# 4_RK3399_EMMC_ADC_PCIE.net
KiCad netlist of a schematic drawn in Altium Designer
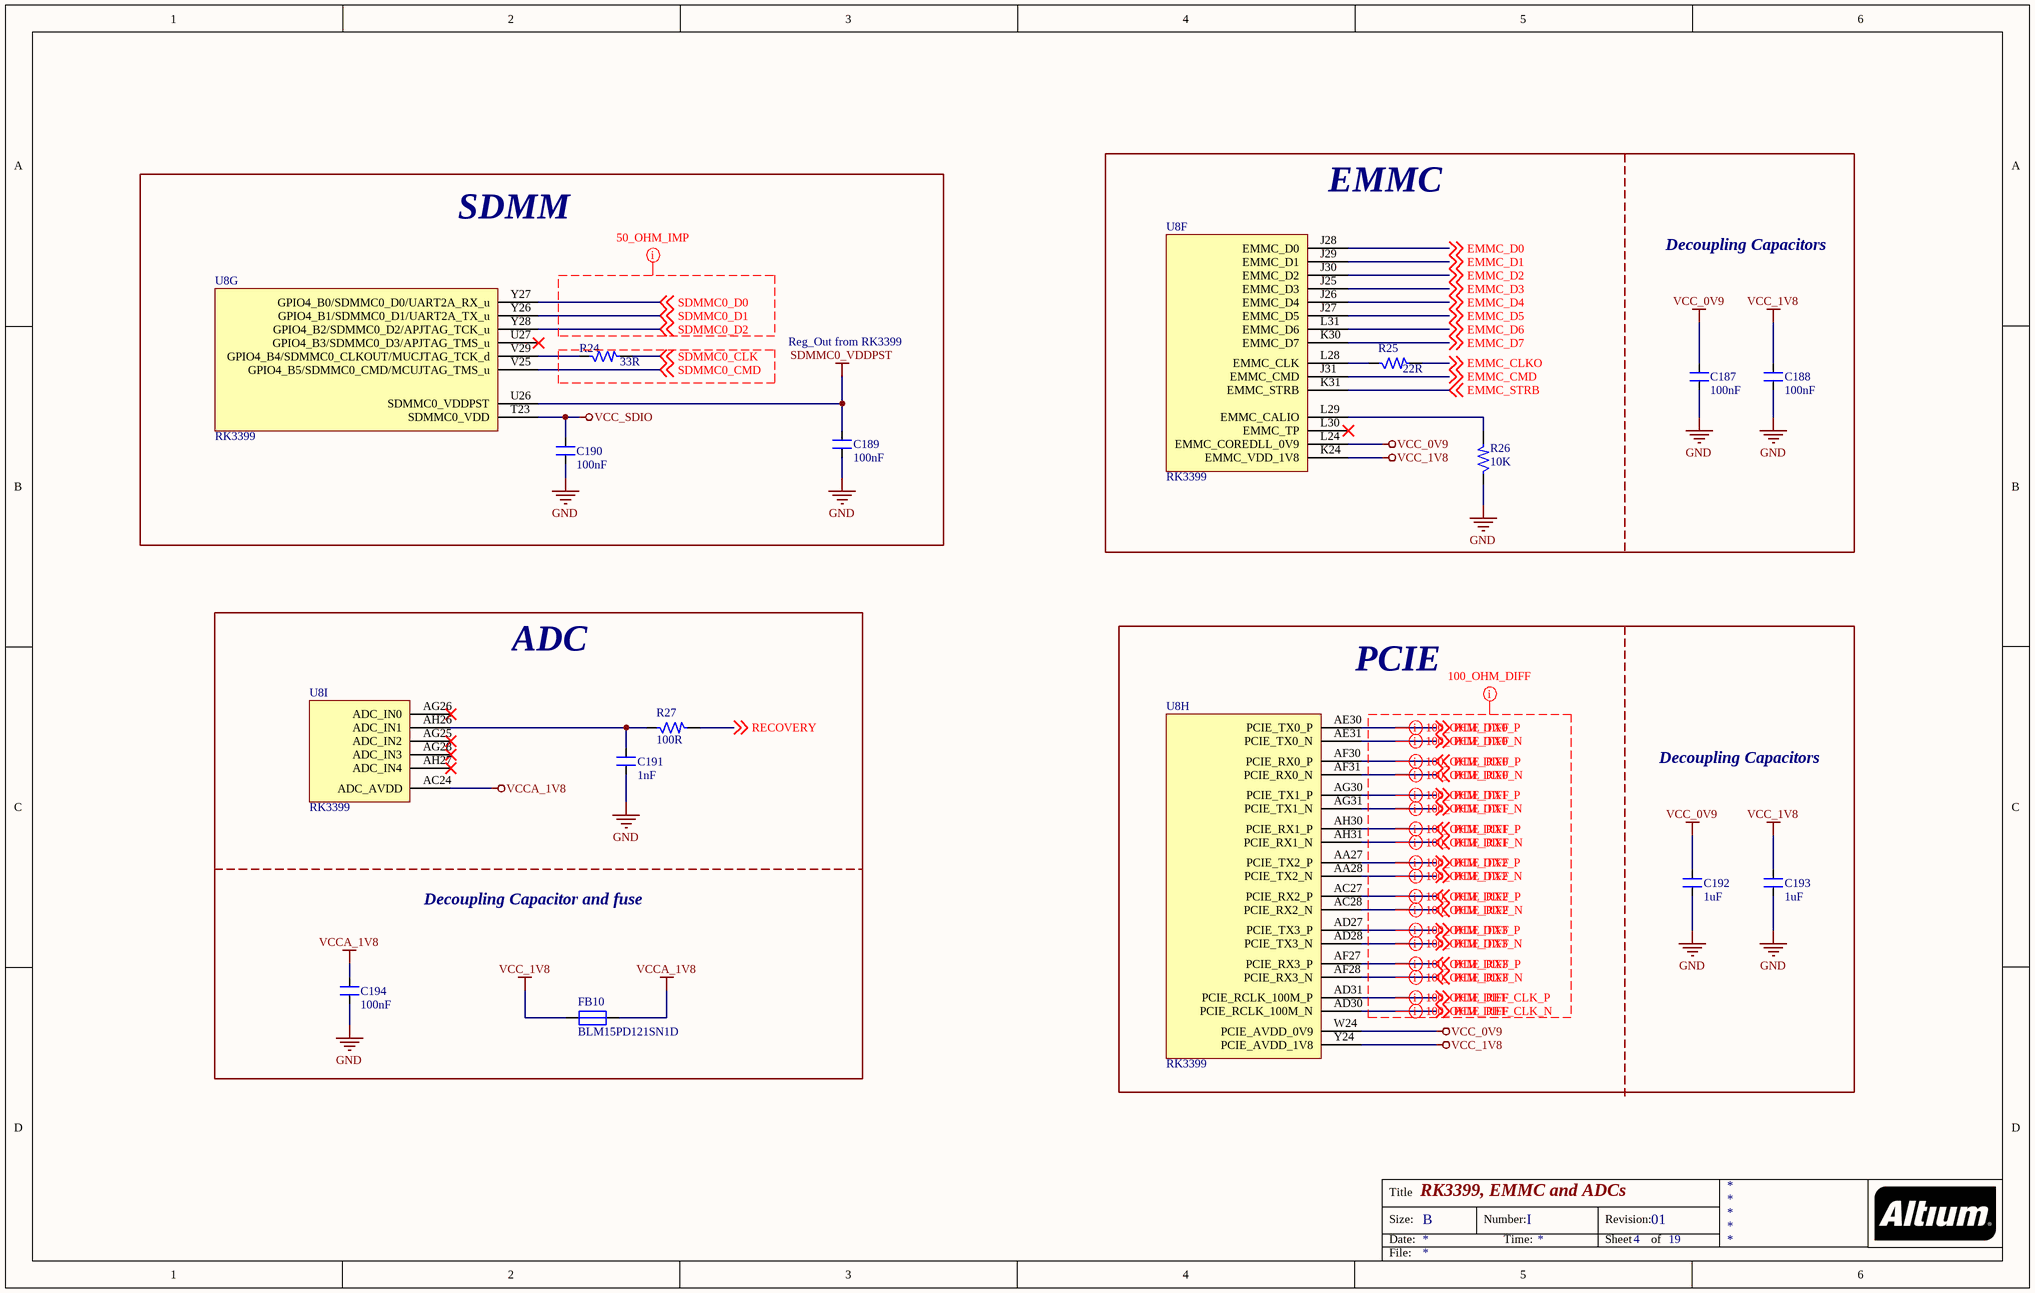
[diagram p0: [4] RK3399_EMMC_ADC_PCIE.SchDoc]

(export (version "E")
  (design (tool "Eeschema 10.0.6"))
  (components
    (comp (ref "C187")
      (value "100nF")
      (footprint "CAP_0201")
      (description "0.1µF ±10% 25V Ceramic Capacitor X5R 0201 (0603 Metric)")
      (fields
        (field (name "MANUFACTURER") "TDK Corporation")
        (field (name "MANUFACTURER PART NUMBER") "C0603X5R1E104K030BB")
      )
      (libsource (lib "EsteemPCB_SOM_Course_intlib") (part "CAP_100nF-25V-10%-0201"))
    )
    (comp (ref "C188")
      (value "100nF")
      (footprint "CAP_0201")
      (description "0.1µF ±10% 25V Ceramic Capacitor X5R 0201 (0603 Metric)")
      (fields
        (field (name "MANUFACTURER") "TDK Corporation")
        (field (name "MANUFACTURER PART NUMBER") "C0603X5R1E104K030BB")
      )
      (libsource (lib "EsteemPCB_SOM_Course_intlib") (part "CAP_100nF-25V-10%-0201"))
    )
    (comp (ref "C189")
      (value "100nF")
      (footprint "CAP_0201")
      (description "0.1µF ±10% 25V Ceramic Capacitor X5R 0201 (0603 Metric)")
      (fields
        (field (name "MANUFACTURER") "TDK Corporation")
        (field (name "MANUFACTURER PART NUMBER") "C0603X5R1E104K030BB")
      )
      (libsource (lib "EsteemPCB_SOM_Course_intlib") (part "CAP_100nF-25V-10%-0201"))
    )
    (comp (ref "C190")
      (value "100nF")
      (footprint "CAP_0201")
      (description "0.1µF ±10% 25V Ceramic Capacitor X5R 0201 (0603 Metric)")
      (fields
        (field (name "MANUFACTURER") "TDK Corporation")
        (field (name "MANUFACTURER PART NUMBER") "C0603X5R1E104K030BB")
      )
      (libsource (lib "EsteemPCB_SOM_Course_intlib") (part "CAP_100nF-25V-10%-0201"))
    )
    (comp (ref "C191")
      (value "1nF")
      (footprint "CAP_0201")
      (description "1000pF ±10% 16V Ceramic Capacitor X7R 0201 (0603 Metric)")
      (fields
        (field (name "MANUFACTURER") "Murata Electronics")
        (field (name "MANUFACTURER PART NUMBER") "GRM033R71C102KA01D")
      )
      (libsource (lib "EsteemPCB_SOM_Course_intlib") (part "CAP_1nF-16V-10%-0201"))
    )
    (comp (ref "C192")
      (value "1uF")
      (footprint "CAP_0201")
      (description "1µF ±20% 16V Ceramic Capacitor X5R 0201 (0603 Metric)")
      (fields
        (field (name "MANUFACTURER") "Samsung Electro-Mechanics")
        (field (name "MANUFACTURER PART NUMBER") "CL03A105MO3NRNH")
      )
      (libsource (lib "EsteemPCB_SOM_Course_intlib") (part "CAP_1uF-16V-10%-0201"))
    )
    (comp (ref "C193")
      (value "1uF")
      (footprint "CAP_0201")
      (description "1µF ±20% 16V Ceramic Capacitor X5R 0201 (0603 Metric)")
      (fields
        (field (name "MANUFACTURER") "Samsung Electro-Mechanics")
        (field (name "MANUFACTURER PART NUMBER") "CL03A105MO3NRNH")
      )
      (libsource (lib "EsteemPCB_SOM_Course_intlib") (part "CAP_1uF-16V-10%-0201"))
    )
    (comp (ref "C194")
      (value "100nF")
      (footprint "CAP_0201")
      (description "0.1µF ±10% 25V Ceramic Capacitor X5R 0201 (0603 Metric)")
      (fields
        (field (name "MANUFACTURER") "TDK Corporation")
        (field (name "MANUFACTURER PART NUMBER") "C0603X5R1E104K030BB")
      )
      (libsource (lib "EsteemPCB_SOM_Course_intlib") (part "CAP_100nF-25V-10%-0201"))
    )
    (comp (ref "FB10")
      (value "BLM15PD121SN1D")
      (footprint "RES_0402")
      (description "120 Ohms @ 100MHz 1 Power Line Ferrite Bead 0402 (1005 Metric) 1.3A 90mOhm")
      (fields (field (name "MANUFACTURER") "Murata Electronics"))
      (libsource (lib "EsteemPCB_SOM_Course_intlib") (part "FB_120R-1.3A-100Mhz-0402"))
    )
    (comp (ref "R24")
      (value "33R")
      (footprint "RES_0201")
      (description "33 Ohms ±1% 0.05W, 1/20W Chip Resistor 0201 (0603 Metric) Thick Film")
      (fields
        (field (name "MANUFACTURER") "Yageo")
        (field (name "MANUFACTURER PART NUMBER") "RC0201FR-0733RL")
      )
      (libsource (lib "EsteemPCB_SOM_Course_intlib") (part "RES_33R-0.05W-1%-0201"))
    )
    (comp (ref "R25")
      (value "22R")
      (footprint "RES_0201")
      (description "22 Ohms ±1% 0.05W, 1/20W Chip Resistor 0201 (0603 Metric) Moisture Resistant Thick Film")
      (fields
        (field (name "MANUFACTURER") "Yageo")
        (field (name "MANUFACTURER PART NUMBER") "RC0201FR-0722RL")
      )
      (libsource (lib "EsteemPCB_SOM_Course_intlib") (part "RES_22R-0.05W-1%-0201"))
    )
    (comp (ref "R26")
      (value "10K")
      (footprint "RES_0201")
      (description "10 kOhms ±1% 0.05W, 1/20W Chip Resistor 0201 (0603 Metric) Thick Film")
      (fields
        (field (name "MANUFACTURER") "Stackpole Electronics Inc")
        (field (name "MANUFACTURER PART NUMBER") "RMCF0201FT10K0")
      )
      (libsource (lib "EsteemPCB_SOM_Course_intlib") (part "RES_10K-0.05W-1%-0201"))
    )
    (comp (ref "R27")
      (value "100R")
      (footprint "RES_0201")
      (description "100 kOhms ±1% 0.05W, 1/20W Chip Resistor 0201 (0603 Metric) Automotive AEC-Q200 Thick Film")
      (fields
        (field (name "MANUFACTURER") "Panasonic Electronic Components")
        (field (name "MANUFACTURER PART NUMBER") "ERJ-1GNF1003C")
      )
      (libsource (lib "EsteemPCB_SOM_Course_intlib") (part "RES_100R-0.05W-1%-0201"))
    )
    (comp (ref "U8")
      (value "RK3399")
      (footprint "FBGA828_23_826X826")
      (description "RK3399 is a low power, high performance processor for computing, personal mobile.")
      (fields (field (name "MANUFACTURER") "Rockchip"))
      (libsource (lib "EsteemPCB_SOM_Course_intlib") (part "IC_RK3399-FCBGA828"))
    )
  )
  (nets
    (net (code "1") (name "EMMC_CLKO") (class "Default")
      (node (ref "R25") (pin "2") (pinfunction "2_2") (pintype "passive"))
    )
    (net (code "2") (name "EMMC_CMD") (class "Default")
      (node (ref "U8") (pin "J31") (pinfunction "EMMC_CMD_J31") (pintype "passive"))
    )
    (net (code "3") (name "EMMC_D0") (class "Default")
      (node (ref "U8") (pin "J28") (pinfunction "EMMC_D0_J28") (pintype "passive"))
    )
    (net (code "4") (name "EMMC_D1") (class "Default")
      (node (ref "U8") (pin "J29") (pinfunction "EMMC_D1_J29") (pintype "passive"))
    )
    (net (code "5") (name "EMMC_D2") (class "Default")
      (node (ref "U8") (pin "J30") (pinfunction "EMMC_D2_J30") (pintype "passive"))
    )
    (net (code "6") (name "EMMC_D3") (class "Default")
      (node (ref "U8") (pin "J25") (pinfunction "EMMC_D3_J25") (pintype "passive"))
    )
    (net (code "7") (name "EMMC_D4") (class "Default")
      (node (ref "U8") (pin "J26") (pinfunction "EMMC_D4_J26") (pintype "passive"))
    )
    (net (code "8") (name "EMMC_D5") (class "Default")
      (node (ref "U8") (pin "J27") (pinfunction "EMMC_D5_J27") (pintype "passive"))
    )
    (net (code "9") (name "EMMC_D6") (class "Default")
      (node (ref "U8") (pin "L31") (pinfunction "EMMC_D6_L31") (pintype "passive"))
    )
    (net (code "10") (name "EMMC_D7") (class "Default")
      (node (ref "U8") (pin "K30") (pinfunction "EMMC_D7_K30") (pintype "passive"))
    )
    (net (code "11") (name "EMMC_STRB") (class "Default")
      (node (ref "U8") (pin "K31") (pinfunction "EMMC_STRB_K31") (pintype "passive"))
    )
    (net (code "12") (name "GND") (class "Default")
      (node (ref "C187") (pin "1") (pinfunction "1_1") (pintype "passive"))
      (node (ref "C188") (pin "1") (pinfunction "1_1") (pintype "passive"))
      (node (ref "C189") (pin "1") (pinfunction "1_1") (pintype "passive"))
      (node (ref "C190") (pin "1") (pinfunction "1_1") (pintype "passive"))
      (node (ref "C191") (pin "1") (pinfunction "1_1") (pintype "passive"))
      (node (ref "C192") (pin "1") (pinfunction "1_1") (pintype "passive"))
      (node (ref "C193") (pin "1") (pinfunction "1_1") (pintype "passive"))
      (node (ref "C194") (pin "1") (pinfunction "1_1") (pintype "passive"))
      (node (ref "R26") (pin "1") (pinfunction "1_1") (pintype "passive"))
    )
    (net (code "13") (name "Net-(U8F-EMMC_CALIO)") (class "Default")
      (node (ref "R26") (pin "2") (pinfunction "2_2") (pintype "passive"))
      (node (ref "U8") (pin "L29") (pinfunction "EMMC_CALIO_L29") (pintype "passive"))
    )
    (net (code "14") (name "Net-(U8F-EMMC_CLK)") (class "Default")
      (node (ref "R25") (pin "1") (pinfunction "1_1") (pintype "passive"))
      (node (ref "U8") (pin "L28") (pinfunction "EMMC_CLK_L28") (pintype "passive"))
    )
    (net (code "15") (name "Net-(U8G-GPIO4_B4{slash}SDMMC0_CLKOUT{slash}MUCJTAG_TCK_d)") (class "Default")
      (node (ref "R24") (pin "1") (pinfunction "1_1") (pintype "passive"))
      (node (ref "U8") (pin "V29") (pinfunction "GPIO4_B4/SDMMC0_CLKOUT/MUCJTAG_TCK_d_V29") (pintype "passive"))
    )
    (net (code "16") (name "Net-(U8I-ADC_IN1)") (class "Default")
      (node (ref "C191") (pin "2") (pinfunction "2_2") (pintype "passive"))
      (node (ref "R27") (pin "1") (pinfunction "1_1") (pintype "passive"))
      (node (ref "U8") (pin "AH26") (pinfunction "ADC_IN1_AH26") (pintype "passive"))
    )
    (net (code "17") (name "PCIE_REF_CLK_N") (class "Default")
      (node (ref "U8") (pin "AD30") (pinfunction "PCIE_RCLK_100M_N_AD30") (pintype "passive"))
    )
    (net (code "18") (name "PCIE_REF_CLK_P") (class "Default")
      (node (ref "U8") (pin "AD31") (pinfunction "PCIE_RCLK_100M_P_AD31") (pintype "passive"))
    )
    (net (code "19") (name "PCIE_RX0_N") (class "Default")
      (node (ref "U8") (pin "AF31") (pinfunction "PCIE_RX0_N_AF31") (pintype "passive"))
    )
    (net (code "20") (name "PCIE_RX0_P") (class "Default")
      (node (ref "U8") (pin "AF30") (pinfunction "PCIE_RX0_P_AF30") (pintype "passive"))
    )
    (net (code "21") (name "PCIE_RX1_N") (class "Default")
      (node (ref "U8") (pin "AH31") (pinfunction "PCIE_RX1_N_AH31") (pintype "passive"))
    )
    (net (code "22") (name "PCIE_RX1_P") (class "Default")
      (node (ref "U8") (pin "AH30") (pinfunction "PCIE_RX1_P_AH30") (pintype "passive"))
    )
    (net (code "23") (name "PCIE_RX2_N") (class "Default")
      (node (ref "U8") (pin "AC28") (pinfunction "PCIE_RX2_N_AC28") (pintype "passive"))
    )
    (net (code "24") (name "PCIE_RX2_P") (class "Default")
      (node (ref "U8") (pin "AC27") (pinfunction "PCIE_RX2_P_AC27") (pintype "passive"))
    )
    (net (code "25") (name "PCIE_RX3_N") (class "Default")
      (node (ref "U8") (pin "AF28") (pinfunction "PCIE_RX3_N_AF28") (pintype "passive"))
    )
    (net (code "26") (name "PCIE_RX3_P") (class "Default")
      (node (ref "U8") (pin "AF27") (pinfunction "PCIE_RX3_P_AF27") (pintype "passive"))
    )
    (net (code "27") (name "PCIE_TX0_N") (class "Default")
      (node (ref "U8") (pin "AE31") (pinfunction "PCIE_TX0_N_AE31") (pintype "passive"))
    )
    (net (code "28") (name "PCIE_TX0_P") (class "Default")
      (node (ref "U8") (pin "AE30") (pinfunction "PCIE_TX0_P_AE30") (pintype "passive"))
    )
    (net (code "29") (name "PCIE_TX1_N") (class "Default")
      (node (ref "U8") (pin "AG31") (pinfunction "PCIE_TX1_N_AG31") (pintype "passive"))
    )
    (net (code "30") (name "PCIE_TX1_P") (class "Default")
      (node (ref "U8") (pin "AG30") (pinfunction "PCIE_TX1_P_AG30") (pintype "passive"))
    )
    (net (code "31") (name "PCIE_TX2_N") (class "Default")
      (node (ref "U8") (pin "AA28") (pinfunction "PCIE_TX2_N_AA28") (pintype "passive"))
    )
    (net (code "32") (name "PCIE_TX2_P") (class "Default")
      (node (ref "U8") (pin "AA27") (pinfunction "PCIE_TX2_P_AA27") (pintype "passive"))
    )
    (net (code "33") (name "PCIE_TX3_N") (class "Default")
      (node (ref "U8") (pin "AD28") (pinfunction "PCIE_TX3_N_AD28") (pintype "passive"))
    )
    (net (code "34") (name "PCIE_TX3_P") (class "Default")
      (node (ref "U8") (pin "AD27") (pinfunction "PCIE_TX3_P_AD27") (pintype "passive"))
    )
    (net (code "35") (name "RECOVERY") (class "Default")
      (node (ref "R27") (pin "2") (pinfunction "2_2") (pintype "passive"))
    )
    (net (code "36") (name "SDMMC0_CLK") (class "Default")
      (node (ref "R24") (pin "2") (pinfunction "2_2") (pintype "passive"))
    )
    (net (code "37") (name "SDMMC0_CMD") (class "Default")
      (node (ref "U8") (pin "V25") (pinfunction "GPIO4_B5/SDMMC0_CMD/MCUJTAG_TMS_u_V25") (pintype "passive"))
    )
    (net (code "38") (name "SDMMC0_D0") (class "Default")
      (node (ref "U8") (pin "Y27") (pinfunction "GPIO4_B0/SDMMC0_D0/UART2A_RX_u_Y27") (pintype "passive"))
    )
    (net (code "39") (name "SDMMC0_D1") (class "Default")
      (node (ref "U8") (pin "Y26") (pinfunction "GPIO4_B1/SDMMC0_D1/UART2A_TX_u_Y26") (pintype "passive"))
    )
    (net (code "40") (name "SDMMC0_D2") (class "Default")
      (node (ref "U8") (pin "Y28") (pinfunction "GPIO4_B2/SDMMC0_D2/APJTAG_TCK_u_Y28") (pintype "passive"))
    )
    (net (code "41") (name "SDMMC0_VDDPST") (class "Default")
      (node (ref "C189") (pin "2") (pinfunction "2_2") (pintype "passive"))
      (node (ref "U8") (pin "U26") (pinfunction "SDMMC0_VDDPST_U26") (pintype "passive"))
    )
    (net (code "42") (name "VCCA_1V8") (class "Default")
      (node (ref "C194") (pin "2") (pinfunction "2_2") (pintype "passive"))
      (node (ref "FB10") (pin "2") (pinfunction "2_2") (pintype "passive"))
      (node (ref "U8") (pin "AC24") (pinfunction "ADC_AVDD_AC24") (pintype "passive"))
    )
    (net (code "43") (name "VCC_0V9") (class "Default")
      (node (ref "C187") (pin "2") (pinfunction "2_2") (pintype "passive"))
      (node (ref "C192") (pin "2") (pinfunction "2_2") (pintype "passive"))
      (node (ref "U8") (pin "L24") (pinfunction "EMMC_COREDLL_0V9_L24") (pintype "passive"))
      (node (ref "U8") (pin "W24") (pinfunction "PCIE_AVDD_0V9_W24") (pintype "passive"))
    )
    (net (code "44") (name "VCC_1V8") (class "Default")
      (node (ref "C188") (pin "2") (pinfunction "2_2") (pintype "passive"))
      (node (ref "C193") (pin "2") (pinfunction "2_2") (pintype "passive"))
      (node (ref "FB10") (pin "1") (pinfunction "1_1") (pintype "passive"))
      (node (ref "U8") (pin "K24") (pinfunction "EMMC_VDD_1V8_K24") (pintype "passive"))
      (node (ref "U8") (pin "Y24") (pinfunction "PCIE_AVDD_1V8_Y24") (pintype "passive"))
    )
    (net (code "45") (name "VCC_SDIO") (class "Default")
      (node (ref "C190") (pin "2") (pinfunction "2_2") (pintype "passive"))
      (node (ref "U8") (pin "T23") (pinfunction "SDMMC0_VDD_T23") (pintype "passive"))
    )
    (net (code "46") (name "unconnected-(U8F-EMMC_TP-PadL30)") (class "Default")
      (node (ref "U8") (pin "L30") (pinfunction "EMMC_TP_L30") (pintype "passive+no_connect"))
    )
    (net (code "47") (name "unconnected-(U8G-GPIO4_B3{slash}SDMMC0_D3{slash}APJTAG_TMS_u-PadU27)") (class "Default")
      (node (ref "U8") (pin "U27") (pinfunction "GPIO4_B3/SDMMC0_D3/APJTAG_TMS_u_U27") (pintype "passive+no_connect"))
    )
    (net (code "48") (name "unconnected-(U8I-ADC_IN0-PadAG26)") (class "Default")
      (node (ref "U8") (pin "AG26") (pinfunction "ADC_IN0_AG26") (pintype "passive+no_connect"))
    )
    (net (code "49") (name "unconnected-(U8I-ADC_IN2-PadAG25)") (class "Default")
      (node (ref "U8") (pin "AG25") (pinfunction "ADC_IN2_AG25") (pintype "passive+no_connect"))
    )
    (net (code "50") (name "unconnected-(U8I-ADC_IN3-PadAG28)") (class "Default")
      (node (ref "U8") (pin "AG28") (pinfunction "ADC_IN3_AG28") (pintype "passive+no_connect"))
    )
    (net (code "51") (name "unconnected-(U8I-ADC_IN4-PadAH27)") (class "Default")
      (node (ref "U8") (pin "AH27") (pinfunction "ADC_IN4_AH27") (pintype "passive+no_connect"))
    )
  )
)
